# McuESP32.net
KiCad netlist of a schematic drawn in Altium Designer
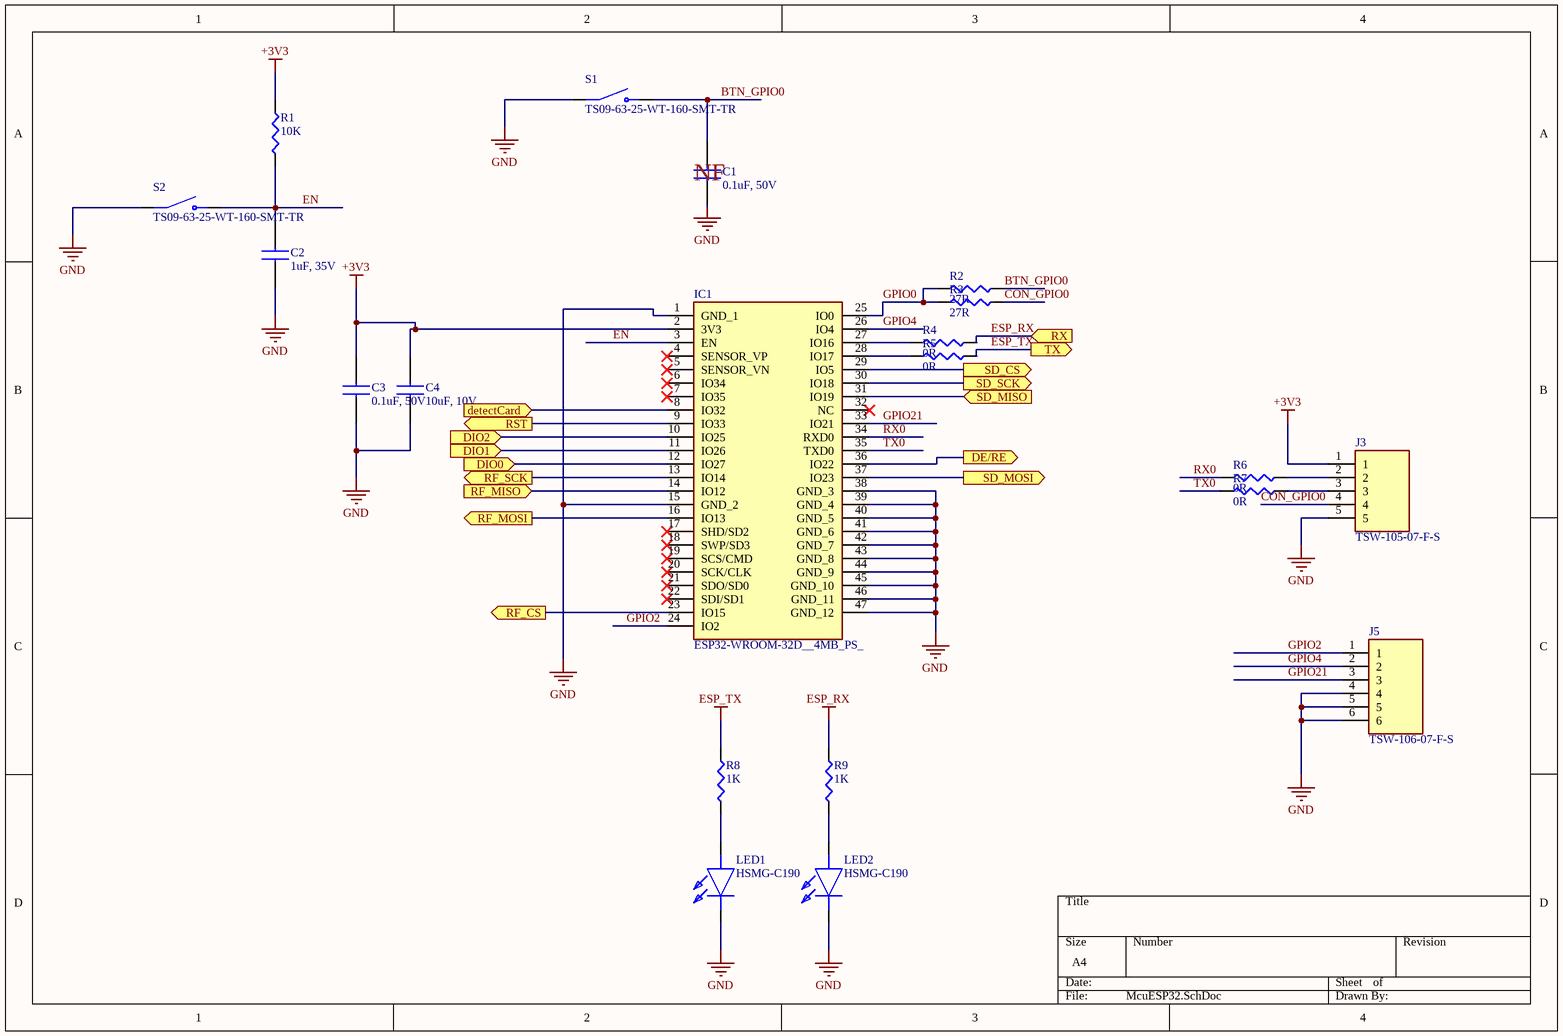
[diagram p0: McuESP32.SchDoc]

(export (version "E")
  (design (tool "Eeschema 10.0.6"))
  (components
    (comp (ref "C1")
      (value "0.1uF, 50V")
      (footprint "SamacSys:CAPC1608X90N")
      (description "CAP CER 0.1UF 50V X7R 0603")
      (fields
        (field (name "MANUFACTURER_PART_NUMBER") "CL10B104KB8NNNL")
        (field (name "MOUSER PART NUMBER") "187-CL10A106MP8NNNC")
      )
      (libsource (lib "SchlibpolyESP") (part "CL10B104KB8NNNL"))
    )
    (comp (ref "C2")
      (value "1uF, 35V")
      (footprint "CAPC1608X90N")
      (fields
        (field (name "MANUFACTURER") "Samsung")
        (field (name "MANUFACTURER PART NUMBER") "CL10A105KL8NNNC")
      )
      (libsource (lib "SchlibpolyESP") (part "CL10A105KL8NNNC"))
    )
    (comp (ref "C3")
      (value "0.1uF, 50V")
      (footprint "SamacSys:CAPC1608X90N")
      (description "CAP CER 0.1UF 50V X7R 0603")
      (fields
        (field (name "MANUFACTURER_PART_NUMBER") "CL10B104KB8NNNL")
        (field (name "MOUSER PART NUMBER") "187-CL10A106MP8NNNC")
      )
      (libsource (lib "SchlibpolyESP") (part "CL10B104KB8NNNL"))
    )
    (comp (ref "C4")
      (value "10uF, 10V")
      (footprint "SamacSys:CAPC1608X90N")
      (description "CAP CER 10UF 10V X5R 0603")
      (fields
        (field (name "MANUFACTURER_PART_NUMBER") "CL10A106MP8NNNC")
        (field (name "MOUSER PART NUMBER") "187-CL10A106MP8NNNC")
      )
      (libsource (lib "SchlibpolyESP") (part "CL10A106MP8NNNC"))
    )
    (comp (ref "IC1")
      (value "ESP32-WROOM-32D__4MB_PS_")
      (footprint "SamacSys:ESP32WROOM32D4MBPS")
      (description "Integrated Circuit")
      (fields
        (field (name "MANUFACTURER_PART_NUMBER") "ESP32-WROOM-32D (4MB PS)")
        (field (name "MOUSER PART NUMBER") "356-ESPWROOM3200PS3")
      )
      (libsource (lib "SchlibPoly") (part "ESP32-WROOM-32D__4MB_PS_"))
    )
    (comp (ref "J3")
      (value "TSW-105-07-F-S")
      (footprint "SamacSys:TSW-105-XX-YY-S")
      (description "Connector")
      (fields (field (name "MOUSER PART NUMBER") "200-TSW10507FS"))
      (libsource (lib "*") (part "TSW-105-07-F-S"))
    )
    (comp (ref "J5")
      (value "TSW-106-07-F-S")
      (footprint "SamacSys:TSW10607FS")
      (description "Connector")
      (fields (field (name "MOUSER PART NUMBER") "200-TSW10607FS"))
      (libsource (lib "SchlibpolyESP") (part "TSW-106-07-F-S"))
    )
    (comp (ref "LED1")
      (value "HSMG-C190")
      (footprint "SamacSys:LEDC1608X90N")
      (description "Green LED 0603 (1608 Metric)")
      (fields (field (name "MOUSER PART NUMBER") "630-HSMG-C190"))
      (libsource (lib "SchlibpolyESP") (part "HSMG-C190"))
    )
    (comp (ref "LED2")
      (value "HSMG-C190")
      (footprint "SamacSys:LEDC1608X90N")
      (description "Green LED 0603 (1608 Metric)")
      (fields (field (name "MOUSER PART NUMBER") "630-HSMG-C190"))
      (libsource (lib "SchlibpolyESP") (part "HSMG-C190"))
    )
    (comp (ref "R1")
      (value "10K")
      (footprint "RESC1607X60N")
      (description "RES 10K OHM 5% 1/10W 0603")
      (fields
        (field (name "MANUFACTURER") "Yageo")
        (field (name "MANUFACTURER PART NUMBER") "RC0603JR-0710KL")
      )
      (libsource (lib "SchlibpolyESP") (part "RC0603JR-0710KL"))
    )
    (comp (ref "R2")
      (value "27R")
      (footprint "RESC1607X60N")
      (description "RES 27 OHM 5% 1/10W 0603")
      (fields
        (field (name "MANUFACTURER") "Yageo")
        (field (name "MANUFACTURER PART NUMBER") "RC0603JR-0727RL")
      )
      (libsource (lib "SchlibpolyESP") (part "RC0603JR-0727RL"))
    )
    (comp (ref "R3")
      (value "27R")
      (footprint "RESC1607X60N")
      (description "RES 27 OHM 5% 1/10W 0603")
      (fields
        (field (name "MANUFACTURER") "Yageo")
        (field (name "MANUFACTURER PART NUMBER") "RC0603JR-0727RL")
      )
      (libsource (lib "SchlibpolyESP") (part "RC0603JR-0727RL"))
    )
    (comp (ref "R4")
      (value "0R")
      (footprint "RESC1607X60N")
      (description "RES 0 OHM JUMPER 1/10W 0603")
      (fields
        (field (name "MANUFACTURER") "Yageo")
        (field (name "MANUFACTURER PART NUMBER") "RC0603JR-070RL")
      )
      (libsource (lib "SchlibpolyESP") (part "RC0603JR-070RL"))
    )
    (comp (ref "R5")
      (value "0R")
      (footprint "RESC1607X60N")
      (description "RES 0 OHM JUMPER 1/10W 0603")
      (fields
        (field (name "MANUFACTURER") "Yageo")
        (field (name "MANUFACTURER PART NUMBER") "RC0603JR-070RL")
      )
      (libsource (lib "SchlibpolyESP") (part "RC0603JR-070RL"))
    )
    (comp (ref "R6")
      (value "0R")
      (footprint "RESC1607X60N")
      (description "RES 0 OHM JUMPER 1/10W 0603")
      (fields
        (field (name "MANUFACTURER") "Yageo")
        (field (name "MANUFACTURER PART NUMBER") "RC0603JR-070RL")
      )
      (libsource (lib "SchlibpolyESP") (part "RC0603JR-070RL"))
    )
    (comp (ref "R7")
      (value "0R")
      (footprint "RESC1607X60N")
      (description "RES 0 OHM JUMPER 1/10W 0603")
      (fields
        (field (name "MANUFACTURER") "Yageo")
        (field (name "MANUFACTURER PART NUMBER") "RC0603JR-070RL")
      )
      (libsource (lib "SchlibpolyESP") (part "RC0603JR-070RL"))
    )
    (comp (ref "R8")
      (value "1K")
      (footprint "RESC1607X60N")
      (description "Fixed Resistor, Thin Film, 0.1W, 1000ohm, 75V, 0.1% +/-Tol, 25ppm/Cel, Surface Mount, 0603")
      (fields
        (field (name "MANUFACTURER") "Yageo")
        (field (name "MANUFACTURER PART NUMBER") "RT0603BRD071KL")
      )
      (libsource (lib "SchlibpolyESP") (part "RT0603BRD071KL"))
    )
    (comp (ref "R9")
      (value "1K")
      (footprint "RESC1607X60N")
      (description "Fixed Resistor, Thin Film, 0.1W, 1000ohm, 75V, 0.1% +/-Tol, 25ppm/Cel, Surface Mount, 0603")
      (fields
        (field (name "MANUFACTURER") "Yageo")
        (field (name "MANUFACTURER PART NUMBER") "RT0603BRD071KL")
      )
      (libsource (lib "SchlibpolyESP") (part "RT0603BRD071KL"))
    )
    (comp (ref "S1")
      (value "TS09-63-25-WT-160-SMT-TR")
      (footprint "SW_TS09-63-25-WT-160-SMT-TR")
      (description "SWITCH TACTILE SPST-NO 0.05A 12V")
      (fields (field (name "MF") "Same Sky"))
      (libsource (lib "SchlibpolyESP") (part "TS09-63-25-WT-160-SMT-TR"))
    )
    (comp (ref "S2")
      (value "TS09-63-25-WT-160-SMT-TR")
      (footprint "SW_TS09-63-25-WT-160-SMT-TR")
      (description "SWITCH TACTILE SPST-NO 0.05A 12V")
      (fields (field (name "MF") "Same Sky"))
      (libsource (lib "SchlibpolyESP") (part "TS09-63-25-WT-160-SMT-TR"))
    )
  )
  (nets
    (net (code "1") (name "+3V3") (class "Default")
      (node (ref "C3") (pin "2") (pinfunction "2_2") (pintype "passive"))
      (node (ref "C4") (pin "1") (pinfunction "1_1") (pintype "passive"))
      (node (ref "IC1") (pin "2") (pinfunction "3V3_2") (pintype "passive"))
      (node (ref "J3") (pin "1") (pinfunction "1_1") (pintype "passive"))
      (node (ref "R1") (pin "2") (pinfunction "2_2") (pintype "passive"))
    )
    (net (code "2") (name "/BTN_GPIO0") (class "Default")
      (node (ref "C1") (pin "2") (pinfunction "2_2") (pintype "passive"))
      (node (ref "R2") (pin "2") (pinfunction "2_2") (pintype "passive"))
      (node (ref "S1") (pin "2") (pinfunction "2_2") (pintype "passive"))
    )
    (net (code "3") (name "/CON_GPIO0") (class "Default")
      (node (ref "J3") (pin "4") (pinfunction "4_4") (pintype "passive"))
      (node (ref "R3") (pin "2") (pinfunction "2_2") (pintype "passive"))
    )
    (net (code "4") (name "/DE{slash}RE") (class "Default")
      (node (ref "IC1") (pin "36") (pinfunction "IO22_36") (pintype "passive"))
    )
    (net (code "5") (name "/DIO0") (class "Default")
      (node (ref "IC1") (pin "12") (pinfunction "IO27_12") (pintype "passive"))
    )
    (net (code "6") (name "/DIO1") (class "Default")
      (node (ref "IC1") (pin "11") (pinfunction "IO26_11") (pintype "passive"))
    )
    (net (code "7") (name "/DIO2") (class "Default")
      (node (ref "IC1") (pin "10") (pinfunction "IO25_10") (pintype "passive"))
    )
    (net (code "8") (name "/EN") (class "Default")
      (node (ref "C2") (pin "2") (pinfunction "2_2") (pintype "passive"))
      (node (ref "IC1") (pin "3") (pinfunction "EN_3") (pintype "passive"))
      (node (ref "R1") (pin "1") (pinfunction "1_1") (pintype "passive"))
      (node (ref "S2") (pin "2") (pinfunction "2_2") (pintype "passive"))
    )
    (net (code "9") (name "/GPIO0") (class "Default")
      (node (ref "IC1") (pin "25") (pinfunction "IO0_25") (pintype "passive"))
      (node (ref "R2") (pin "1") (pinfunction "1_1") (pintype "passive"))
      (node (ref "R3") (pin "1") (pinfunction "1_1") (pintype "passive"))
    )
    (net (code "10") (name "/GPIO2") (class "Default")
      (node (ref "IC1") (pin "24") (pinfunction "IO2_24") (pintype "passive"))
      (node (ref "J5") (pin "1") (pinfunction "1_1") (pintype "passive"))
    )
    (net (code "11") (name "/GPIO4") (class "Default")
      (node (ref "IC1") (pin "26") (pinfunction "IO4_26") (pintype "passive"))
      (node (ref "J5") (pin "2") (pinfunction "2_2") (pintype "passive"))
    )
    (net (code "12") (name "/GPIO21") (class "Default")
      (node (ref "IC1") (pin "33") (pinfunction "IO21_33") (pintype "passive"))
      (node (ref "J5") (pin "3") (pinfunction "3_3") (pintype "passive"))
    )
    (net (code "13") (name "/RF_CS") (class "Default")
      (node (ref "IC1") (pin "23") (pinfunction "IO15_23") (pintype "passive"))
    )
    (net (code "14") (name "/RF_MISO") (class "Default")
      (node (ref "IC1") (pin "14") (pinfunction "IO12_14") (pintype "passive"))
    )
    (net (code "15") (name "/RF_MOSI") (class "Default")
      (node (ref "IC1") (pin "16") (pinfunction "IO13_16") (pintype "passive"))
    )
    (net (code "16") (name "/RF_SCK") (class "Default")
      (node (ref "IC1") (pin "13") (pinfunction "IO14_13") (pintype "passive"))
    )
    (net (code "17") (name "/RST") (class "Default")
      (node (ref "IC1") (pin "9") (pinfunction "IO33_9") (pintype "passive"))
    )
    (net (code "18") (name "/RX0") (class "Default")
      (node (ref "IC1") (pin "34") (pinfunction "RXD0_34") (pintype "passive"))
      (node (ref "R6") (pin "1") (pinfunction "1_1") (pintype "passive"))
    )
    (net (code "19") (name "/SD_CS") (class "Default")
      (node (ref "IC1") (pin "29") (pinfunction "IO5_29") (pintype "passive"))
    )
    (net (code "20") (name "/SD_MISO") (class "Default")
      (node (ref "IC1") (pin "31") (pinfunction "IO19_31") (pintype "passive"))
    )
    (net (code "21") (name "/SD_MOSI") (class "Default")
      (node (ref "IC1") (pin "37") (pinfunction "IO23_37") (pintype "passive"))
    )
    (net (code "22") (name "/SD_SCK") (class "Default")
      (node (ref "IC1") (pin "30") (pinfunction "IO18_30") (pintype "passive"))
    )
    (net (code "23") (name "/TX0") (class "Default")
      (node (ref "IC1") (pin "35") (pinfunction "TXD0_35") (pintype "passive"))
      (node (ref "R7") (pin "1") (pinfunction "1_1") (pintype "passive"))
    )
    (net (code "24") (name "/detectCard") (class "Default")
      (node (ref "IC1") (pin "8") (pinfunction "IO32_8") (pintype "passive"))
    )
    (net (code "25") (name "ESP_RX") (class "Default")
      (node (ref "R4") (pin "2") (pinfunction "2_2") (pintype "passive"))
      (node (ref "R9") (pin "2") (pinfunction "2_2") (pintype "passive"))
    )
    (net (code "26") (name "ESP_TX") (class "Default")
      (node (ref "R5") (pin "2") (pinfunction "2_2") (pintype "passive"))
      (node (ref "R8") (pin "2") (pinfunction "2_2") (pintype "passive"))
    )
    (net (code "27") (name "GND") (class "Default")
      (node (ref "C1") (pin "1") (pinfunction "1_1") (pintype "passive"))
      (node (ref "C2") (pin "1") (pinfunction "1_1") (pintype "passive"))
      (node (ref "C3") (pin "1") (pinfunction "1_1") (pintype "passive"))
      (node (ref "C4") (pin "2") (pinfunction "2_2") (pintype "passive"))
      (node (ref "IC1") (pin "1") (pinfunction "GND_1_1") (pintype "passive"))
      (node (ref "IC1") (pin "15") (pinfunction "GND_2_15") (pintype "passive"))
      (node (ref "IC1") (pin "38") (pinfunction "GND_3_38") (pintype "passive"))
      (node (ref "IC1") (pin "39") (pinfunction "GND_4_39") (pintype "passive"))
      (node (ref "IC1") (pin "40") (pinfunction "GND_5_40") (pintype "passive"))
      (node (ref "IC1") (pin "41") (pinfunction "GND_6_41") (pintype "passive"))
      (node (ref "IC1") (pin "42") (pinfunction "GND_7_42") (pintype "passive"))
      (node (ref "IC1") (pin "43") (pinfunction "GND_8_43") (pintype "passive"))
      (node (ref "IC1") (pin "44") (pinfunction "GND_9_44") (pintype "passive"))
      (node (ref "IC1") (pin "45") (pinfunction "GND_10_45") (pintype "passive"))
      (node (ref "IC1") (pin "46") (pinfunction "GND_11_46") (pintype "passive"))
      (node (ref "IC1") (pin "47") (pinfunction "GND_12_47") (pintype "passive"))
      (node (ref "J3") (pin "5") (pinfunction "5_5") (pintype "passive"))
      (node (ref "J5") (pin "4") (pinfunction "4_4") (pintype "passive"))
      (node (ref "J5") (pin "5") (pinfunction "5_5") (pintype "passive"))
      (node (ref "J5") (pin "6") (pinfunction "6_6") (pintype "passive"))
      (node (ref "LED1") (pin "1") (pinfunction "K_1") (pintype "passive"))
      (node (ref "LED2") (pin "1") (pinfunction "K_1") (pintype "passive"))
      (node (ref "S1") (pin "1") (pinfunction "1_1") (pintype "passive"))
      (node (ref "S2") (pin "1") (pinfunction "1_1") (pintype "passive"))
    )
    (net (code "28") (name "Net-(IC1-IO16)") (class "Default")
      (node (ref "IC1") (pin "27") (pinfunction "IO16_27") (pintype "passive"))
      (node (ref "R4") (pin "1") (pinfunction "1_1") (pintype "passive"))
    )
    (net (code "29") (name "Net-(IC1-IO17)") (class "Default")
      (node (ref "IC1") (pin "28") (pinfunction "IO17_28") (pintype "passive"))
      (node (ref "R5") (pin "1") (pinfunction "1_1") (pintype "passive"))
    )
    (net (code "30") (name "Net-(J3-Pad2)") (class "Default")
      (node (ref "J3") (pin "2") (pinfunction "2_2") (pintype "passive"))
      (node (ref "R6") (pin "2") (pinfunction "2_2") (pintype "passive"))
    )
    (net (code "31") (name "Net-(J3-Pad3)") (class "Default")
      (node (ref "J3") (pin "3") (pinfunction "3_3") (pintype "passive"))
      (node (ref "R7") (pin "2") (pinfunction "2_2") (pintype "passive"))
    )
    (net (code "32") (name "Net-(LED1-A)") (class "Default")
      (node (ref "LED1") (pin "2") (pinfunction "A_2") (pintype "passive"))
      (node (ref "R8") (pin "1") (pinfunction "1_1") (pintype "passive"))
    )
    (net (code "33") (name "Net-(LED2-A)") (class "Default")
      (node (ref "LED2") (pin "2") (pinfunction "A_2") (pintype "passive"))
      (node (ref "R9") (pin "1") (pinfunction "1_1") (pintype "passive"))
    )
    (net (code "34") (name "unconnected-(IC1-IO34-Pad6)") (class "Default")
      (node (ref "IC1") (pin "6") (pinfunction "IO34_6") (pintype "passive+no_connect"))
    )
    (net (code "35") (name "unconnected-(IC1-IO35-Pad7)") (class "Default")
      (node (ref "IC1") (pin "7") (pinfunction "IO35_7") (pintype "passive+no_connect"))
    )
    (net (code "36") (name "unconnected-(IC1-NC-Pad32)") (class "Default")
      (node (ref "IC1") (pin "32") (pinfunction "NC_32") (pintype "passive+no_connect"))
    )
    (net (code "37") (name "unconnected-(IC1-SCK{slash}CLK-Pad20)") (class "Default")
      (node (ref "IC1") (pin "20") (pinfunction "SCK/CLK_20") (pintype "passive+no_connect"))
    )
    (net (code "38") (name "unconnected-(IC1-SCS{slash}CMD-Pad19)") (class "Default")
      (node (ref "IC1") (pin "19") (pinfunction "SCS/CMD_19") (pintype "passive+no_connect"))
    )
    (net (code "39") (name "unconnected-(IC1-SDI{slash}SD1-Pad22)") (class "Default")
      (node (ref "IC1") (pin "22") (pinfunction "SDI/SD1_22") (pintype "passive+no_connect"))
    )
    (net (code "40") (name "unconnected-(IC1-SDO{slash}SD0-Pad21)") (class "Default")
      (node (ref "IC1") (pin "21") (pinfunction "SDO/SD0_21") (pintype "passive+no_connect"))
    )
    (net (code "41") (name "unconnected-(IC1-SENSOR_VN-Pad5)") (class "Default")
      (node (ref "IC1") (pin "5") (pinfunction "SENSOR_VN_5") (pintype "passive+no_connect"))
    )
    (net (code "42") (name "unconnected-(IC1-SENSOR_VP-Pad4)") (class "Default")
      (node (ref "IC1") (pin "4") (pinfunction "SENSOR_VP_4") (pintype "passive+no_connect"))
    )
    (net (code "43") (name "unconnected-(IC1-SHD{slash}SD2-Pad17)") (class "Default")
      (node (ref "IC1") (pin "17") (pinfunction "SHD/SD2_17") (pintype "passive+no_connect"))
    )
    (net (code "44") (name "unconnected-(IC1-SWP{slash}SD3-Pad18)") (class "Default")
      (node (ref "IC1") (pin "18") (pinfunction "SWP/SD3_18") (pintype "passive+no_connect"))
    )
  )
)
